# LTC2473CDR1.net
KiCad netlist of a schematic drawn in EAGLE
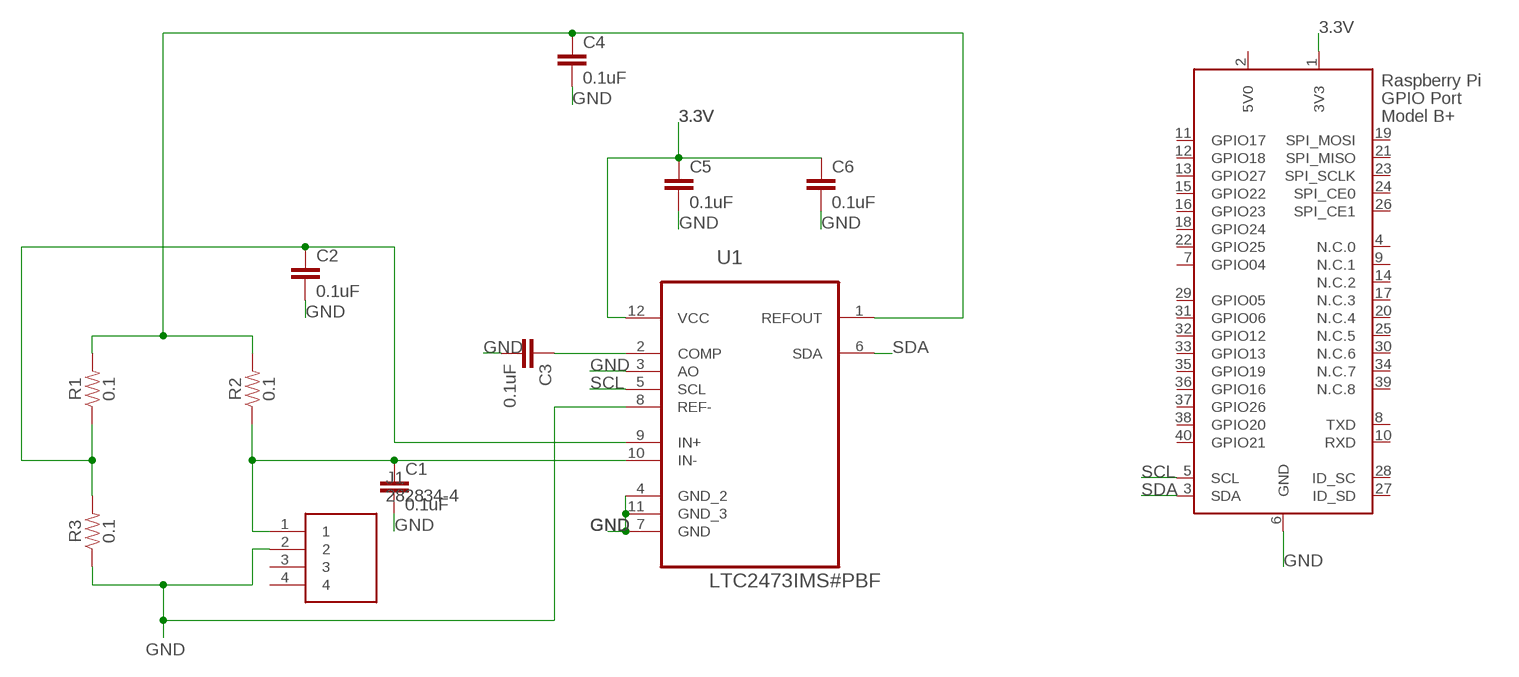
[diagram p0: schematic, sheet 1]

(export (version "E")
  (design (tool "Eeschema 10.0.6"))
  (components
    (comp (ref "C1")
      (value "0.1uF")
      (footprint "eagle-import:0603")
      (libsource (lib "eagle-import") (part "0.1UF-0603-25V-(+80/-20%)"))
    )
    (comp (ref "C2")
      (value "0.1uF")
      (footprint "eagle-import:0603")
      (libsource (lib "eagle-import") (part "0.1UF-0603-25V-(+80/-20%)"))
    )
    (comp (ref "C3")
      (value "0.1uF")
      (footprint "eagle-import:0603")
      (libsource (lib "eagle-import") (part "0.1UF-0603-25V-(+80/-20%)"))
    )
    (comp (ref "C4")
      (value "0.1uF")
      (footprint "eagle-import:0603")
      (libsource (lib "eagle-import") (part "0.1UF-0603-25V-(+80/-20%)"))
    )
    (comp (ref "C5")
      (value "0.1uF")
      (footprint "eagle-import:0603")
      (libsource (lib "eagle-import") (part "0.1UF-0603-25V-(+80/-20%)"))
    )
    (comp (ref "C6")
      (value "0.1uF")
      (footprint "eagle-import:0603")
      (libsource (lib "eagle-import") (part "0.1UF-0603-25V-(+80/-20%)"))
    )
    (comp (ref "J1")
      (value "282834-4")
      (footprint "eagle-import:2828344")
      (fields (field (name "MOUSER_PART_NUMBER") "571-282834-4"))
      (libsource (lib "eagle-import") (part "282834-4"))
    )
    (comp (ref "R1")
      (value "0.1")
      (footprint "eagle-import:0603")
      (libsource (lib "eagle-import") (part "0.1OHM-0603-1/3W-1%"))
    )
    (comp (ref "R2")
      (value "0.1")
      (footprint "eagle-import:0603")
      (libsource (lib "eagle-import") (part "0.1OHM-0603-1/3W-1%"))
    )
    (comp (ref "R3")
      (value "0.1")
      (footprint "eagle-import:0603")
      (libsource (lib "eagle-import") (part "0.1OHM-0603-1/3W-1%"))
    )
    (comp (ref "U1")
      (value "LTC2473IMS#PBF")
      (footprint "eagle-import:SOP65P490X110-12N")
      (fields (field (name "MF") "Analog Devices"))
      (libsource (lib "eagle-import") (part "LTC2473IMS#PBF"))
    )
    (comp (ref "X1")
      (value "RASPI_BOARD_B+_HDC")
      (footprint "eagle-import:RASPI_BOARD_B+HAT_DF_CF")
      (libsource (lib "eagle-import") (part "RASPI_BOARD_B+_HDC"))
    )
  )
  (nets
    (net (code "1") (name "/3.3V") (class "Default")
      (node (ref "C5") (pin "1") (pinfunction "1_1") (pintype "passive"))
      (node (ref "C6") (pin "1") (pinfunction "1_1") (pintype "passive"))
      (node (ref "U1") (pin "12") (pinfunction "VCC_12") (pintype "power_in"))
      (node (ref "X1") (pin "1") (pinfunction "3V3_1") (pintype "power_in"))
    )
    (net (code "2") (name "/5V0") (class "Default")
      (node (ref "X1") (pin "2") (pinfunction "5V0_2") (pintype "power_in"))
    )
    (net (code "3") (name "/GND") (class "Default")
      (node (ref "C1") (pin "2") (pinfunction "2_2") (pintype "passive"))
      (node (ref "C2") (pin "2") (pinfunction "2_2") (pintype "passive"))
      (node (ref "C3") (pin "2") (pinfunction "2_2") (pintype "passive"))
      (node (ref "C4") (pin "2") (pinfunction "2_2") (pintype "passive"))
      (node (ref "C5") (pin "2") (pinfunction "2_2") (pintype "passive"))
      (node (ref "C6") (pin "2") (pinfunction "2_2") (pintype "passive"))
      (node (ref "J1") (pin "2") (pinfunction "2_2") (pintype "bidirectional"))
      (node (ref "R3") (pin "1") (pinfunction "1_1") (pintype "passive"))
      (node (ref "U1") (pin "11") (pinfunction "GND_3_11") (pintype "passive"))
      (node (ref "U1") (pin "3") (pinfunction "AO_3") (pintype "input"))
      (node (ref "U1") (pin "4") (pinfunction "GND_2_4") (pintype "passive"))
      (node (ref "U1") (pin "7") (pinfunction "GND_7") (pintype "passive"))
      (node (ref "U1") (pin "8") (pinfunction "REF-_8") (pintype "input"))
      (node (ref "X1") (pin "6") (pinfunction "GND_6") (pintype "power_in"))
    )
    (net (code "4") (name "/SCL") (class "Default")
      (node (ref "U1") (pin "5") (pinfunction "SCL_5") (pintype "input"))
      (node (ref "X1") (pin "5") (pinfunction "SCL_5") (pintype "bidirectional"))
    )
    (net (code "5") (name "/SDA") (class "Default")
      (node (ref "U1") (pin "6") (pinfunction "SDA_6") (pintype "bidirectional"))
      (node (ref "X1") (pin "3") (pinfunction "SDA_3") (pintype "bidirectional"))
    )
    (net (code "6") (name "Net-(U1-COMP)") (class "Default")
      (node (ref "C3") (pin "1") (pinfunction "1_1") (pintype "passive"))
      (node (ref "U1") (pin "2") (pinfunction "COMP_2") (pintype "input"))
    )
    (net (code "7") (name "Net-(U1-IN+)") (class "Default")
      (node (ref "C2") (pin "1") (pinfunction "1_1") (pintype "passive"))
      (node (ref "R1") (pin "1") (pinfunction "1_1") (pintype "passive"))
      (node (ref "R3") (pin "2") (pinfunction "2_2") (pintype "passive"))
      (node (ref "U1") (pin "9") (pinfunction "IN+_9") (pintype "input"))
    )
    (net (code "8") (name "Net-(U1-IN-)") (class "Default")
      (node (ref "C1") (pin "1") (pinfunction "1_1") (pintype "passive"))
      (node (ref "J1") (pin "1") (pinfunction "1_1") (pintype "bidirectional"))
      (node (ref "R2") (pin "1") (pinfunction "1_1") (pintype "passive"))
      (node (ref "U1") (pin "10") (pinfunction "IN-_10") (pintype "input"))
    )
    (net (code "9") (name "Net-(U1-REFOUT)") (class "Default")
      (node (ref "C4") (pin "1") (pinfunction "1_1") (pintype "passive"))
      (node (ref "R1") (pin "2") (pinfunction "2_2") (pintype "passive"))
      (node (ref "R2") (pin "2") (pinfunction "2_2") (pintype "passive"))
      (node (ref "U1") (pin "1") (pinfunction "REFOUT_1") (pintype "output"))
    )
    (net (code "10") (name "unconnected-(J1-Pad3)") (class "Default")
      (node (ref "J1") (pin "3") (pinfunction "3_3") (pintype "bidirectional"))
    )
    (net (code "11") (name "unconnected-(J1-Pad4)") (class "Default")
      (node (ref "J1") (pin "4") (pinfunction "4_4") (pintype "bidirectional"))
    )
    (net (code "12") (name "unconnected-(X1-GPIO04-Pad7)") (class "Default")
      (node (ref "X1") (pin "7") (pinfunction "GPIO04_7") (pintype "bidirectional"))
    )
    (net (code "13") (name "unconnected-(X1-GPIO05-Pad29)") (class "Default")
      (node (ref "X1") (pin "29") (pinfunction "GPIO05_29") (pintype "no_connect"))
    )
    (net (code "14") (name "unconnected-(X1-GPIO06-Pad31)") (class "Default")
      (node (ref "X1") (pin "31") (pinfunction "GPIO06_31") (pintype "no_connect"))
    )
    (net (code "15") (name "unconnected-(X1-GPIO12-Pad32)") (class "Default")
      (node (ref "X1") (pin "32") (pinfunction "GPIO12_32") (pintype "no_connect"))
    )
    (net (code "16") (name "unconnected-(X1-GPIO13-Pad33)") (class "Default")
      (node (ref "X1") (pin "33") (pinfunction "GPIO13_33") (pintype "no_connect"))
    )
    (net (code "17") (name "unconnected-(X1-GPIO16-Pad36)") (class "Default")
      (node (ref "X1") (pin "36") (pinfunction "GPIO16_36") (pintype "no_connect"))
    )
    (net (code "18") (name "unconnected-(X1-GPIO17-Pad11)") (class "Default")
      (node (ref "X1") (pin "11") (pinfunction "GPIO17_11") (pintype "bidirectional"))
    )
    (net (code "19") (name "unconnected-(X1-GPIO18-Pad12)") (class "Default")
      (node (ref "X1") (pin "12") (pinfunction "GPIO18_12") (pintype "bidirectional"))
    )
    (net (code "20") (name "unconnected-(X1-GPIO19-Pad35)") (class "Default")
      (node (ref "X1") (pin "35") (pinfunction "GPIO19_35") (pintype "no_connect"))
    )
    (net (code "21") (name "unconnected-(X1-GPIO20-Pad38)") (class "Default")
      (node (ref "X1") (pin "38") (pinfunction "GPIO20_38") (pintype "no_connect"))
    )
    (net (code "22") (name "unconnected-(X1-GPIO21-Pad40)") (class "Default")
      (node (ref "X1") (pin "40") (pinfunction "GPIO21_40") (pintype "no_connect"))
    )
    (net (code "23") (name "unconnected-(X1-GPIO22-Pad15)") (class "Default")
      (node (ref "X1") (pin "15") (pinfunction "GPIO22_15") (pintype "bidirectional"))
    )
    (net (code "24") (name "unconnected-(X1-GPIO23-Pad16)") (class "Default")
      (node (ref "X1") (pin "16") (pinfunction "GPIO23_16") (pintype "bidirectional"))
    )
    (net (code "25") (name "unconnected-(X1-GPIO24-Pad18)") (class "Default")
      (node (ref "X1") (pin "18") (pinfunction "GPIO24_18") (pintype "bidirectional"))
    )
    (net (code "26") (name "unconnected-(X1-GPIO25-Pad22)") (class "Default")
      (node (ref "X1") (pin "22") (pinfunction "GPIO25_22") (pintype "bidirectional"))
    )
    (net (code "27") (name "unconnected-(X1-GPIO26-Pad37)") (class "Default")
      (node (ref "X1") (pin "37") (pinfunction "GPIO26_37") (pintype "no_connect"))
    )
    (net (code "28") (name "unconnected-(X1-GPIO27-Pad13)") (class "Default")
      (node (ref "X1") (pin "13") (pinfunction "GPIO27_13") (pintype "bidirectional"))
    )
    (net (code "29") (name "unconnected-(X1-ID_SC-Pad28)") (class "Default")
      (node (ref "X1") (pin "28") (pinfunction "ID_SC_28") (pintype "no_connect"))
    )
    (net (code "30") (name "unconnected-(X1-ID_SD-Pad27)") (class "Default")
      (node (ref "X1") (pin "27") (pinfunction "ID_SD_27") (pintype "no_connect"))
    )
    (net (code "31") (name "unconnected-(X1-N.C.0-Pad4)") (class "Default")
      (node (ref "X1") (pin "4") (pinfunction "N.C.0_4") (pintype "no_connect"))
    )
    (net (code "32") (name "unconnected-(X1-N.C.1-Pad9)") (class "Default")
      (node (ref "X1") (pin "9") (pinfunction "N.C.1_9") (pintype "no_connect"))
    )
    (net (code "33") (name "unconnected-(X1-N.C.2-Pad14)") (class "Default")
      (node (ref "X1") (pin "14") (pinfunction "N.C.2_14") (pintype "no_connect"))
    )
    (net (code "34") (name "unconnected-(X1-N.C.3-Pad17)") (class "Default")
      (node (ref "X1") (pin "17") (pinfunction "N.C.3_17") (pintype "no_connect"))
    )
    (net (code "35") (name "unconnected-(X1-N.C.4-Pad20)") (class "Default")
      (node (ref "X1") (pin "20") (pinfunction "N.C.4_20") (pintype "no_connect"))
    )
    (net (code "36") (name "unconnected-(X1-N.C.5-Pad25)") (class "Default")
      (node (ref "X1") (pin "25") (pinfunction "N.C.5_25") (pintype "no_connect"))
    )
    (net (code "37") (name "unconnected-(X1-N.C.6-Pad30)") (class "Default")
      (node (ref "X1") (pin "30") (pinfunction "N.C.6_30") (pintype "no_connect"))
    )
    (net (code "38") (name "unconnected-(X1-N.C.7-Pad34)") (class "Default")
      (node (ref "X1") (pin "34") (pinfunction "N.C.7_34") (pintype "no_connect"))
    )
    (net (code "39") (name "unconnected-(X1-N.C.8-Pad39)") (class "Default")
      (node (ref "X1") (pin "39") (pinfunction "N.C.8_39") (pintype "no_connect"))
    )
    (net (code "40") (name "unconnected-(X1-RXD-Pad10)") (class "Default")
      (node (ref "X1") (pin "10") (pinfunction "RXD_10") (pintype "bidirectional"))
    )
    (net (code "41") (name "unconnected-(X1-SPI_CE0-Pad24)") (class "Default")
      (node (ref "X1") (pin "24") (pinfunction "SPI_CE0_24") (pintype "bidirectional"))
    )
    (net (code "42") (name "unconnected-(X1-SPI_CE1-Pad26)") (class "Default")
      (node (ref "X1") (pin "26") (pinfunction "SPI_CE1_26") (pintype "bidirectional"))
    )
    (net (code "43") (name "unconnected-(X1-SPI_MISO-Pad21)") (class "Default")
      (node (ref "X1") (pin "21") (pinfunction "SPI_MISO_21") (pintype "bidirectional"))
    )
    (net (code "44") (name "unconnected-(X1-SPI_MOSI-Pad19)") (class "Default")
      (node (ref "X1") (pin "19") (pinfunction "SPI_MOSI_19") (pintype "bidirectional"))
    )
    (net (code "45") (name "unconnected-(X1-SPI_SCLK-Pad23)") (class "Default")
      (node (ref "X1") (pin "23") (pinfunction "SPI_SCLK_23") (pintype "bidirectional"))
    )
    (net (code "46") (name "unconnected-(X1-TXD-Pad8)") (class "Default")
      (node (ref "X1") (pin "8") (pinfunction "TXD_8") (pintype "bidirectional"))
    )
  )
)
